# design.net
KiCad netlist of a schematic drawn in Altium Designer
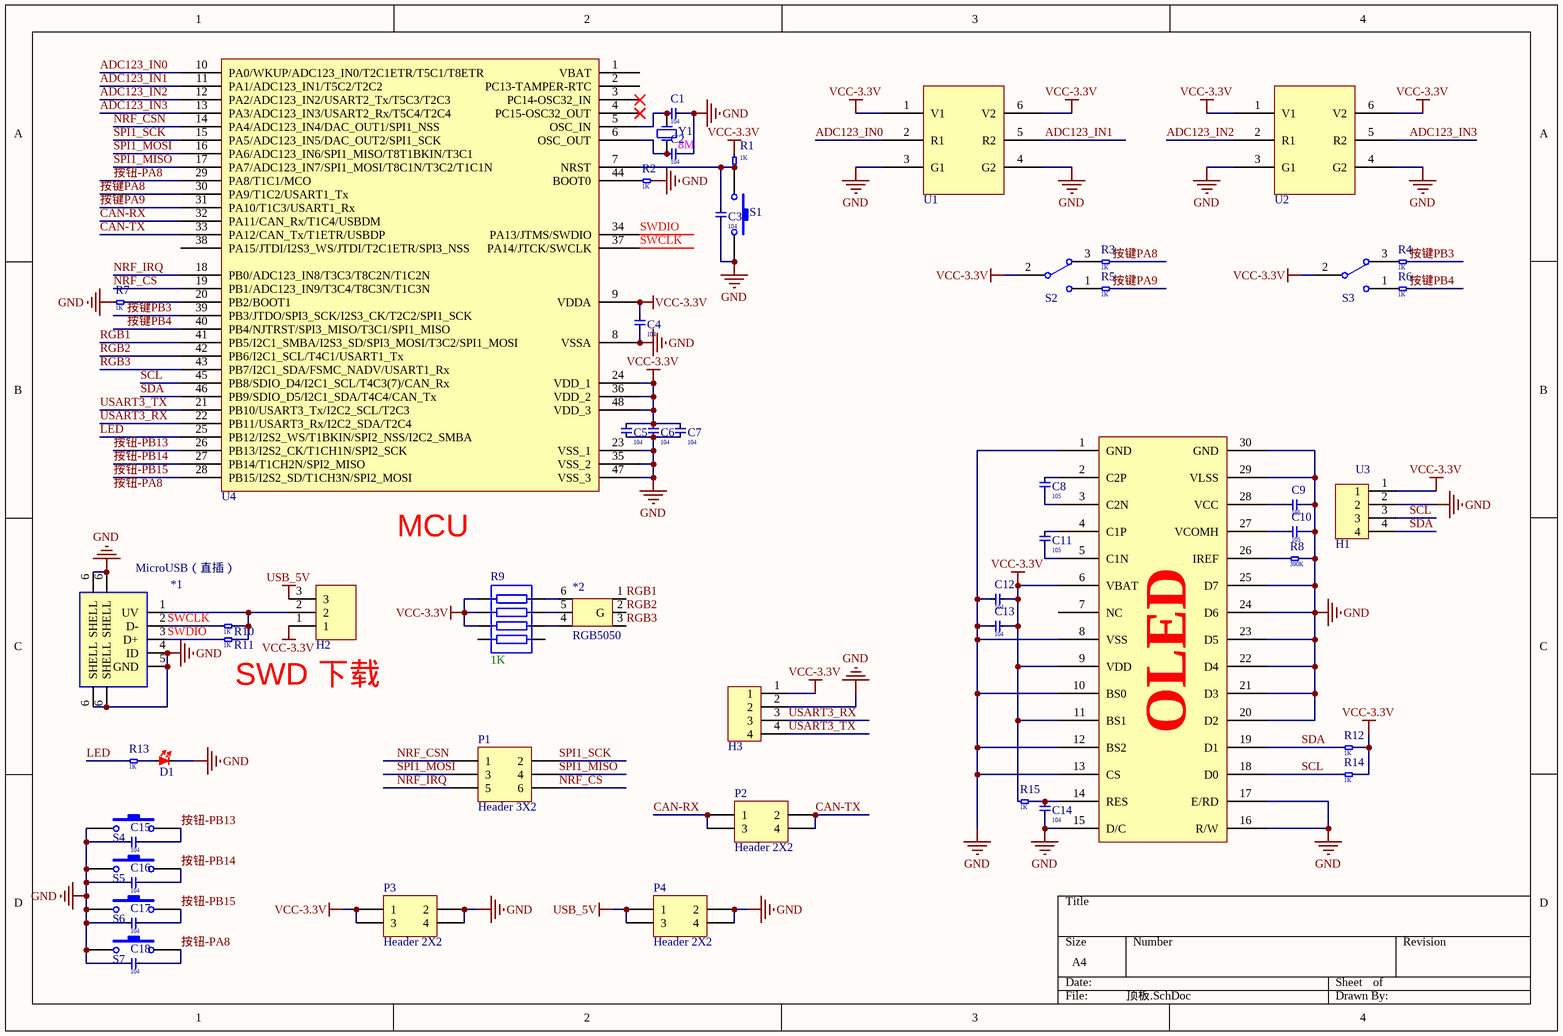
[diagram p0: 顶板.SchDoc]

(export (version "E")
  (design (tool "Eeschema 10.0.6"))
  (components
    (comp (ref "*1")
      (value "MicroUSB（直插）")
      (footprint "MicroUSB（直插）")
      (libsource (lib "固执啊啊啊啊啊（方林的封装库）7.24") (part "MicroUSB（直插）"))
    )
    (comp (ref "*2")
      (value "RGB5050")
      (footprint "RGB5050")
      (libsource (lib "xiaoze_Library") (part "RGB5050"))
    )
    (comp (ref "C1")
      (value "CAP0603")
      (footprint "CAP0603")
      (fields (field (name "ALTIUM_UNNAMED_1") "104"))
      (libsource (lib "固执啊啊啊啊啊（方林的封装库）7.24") (part "CAP0603"))
    )
    (comp (ref "C2")
      (value "CAP0603")
      (footprint "CAP0603")
      (fields (field (name "ALTIUM_UNNAMED_1") "104"))
      (libsource (lib "固执啊啊啊啊啊（方林的封装库）7.24") (part "CAP0603"))
    )
    (comp (ref "C3")
      (value "CAP0603")
      (footprint "CAP0603")
      (fields (field (name "ALTIUM_UNNAMED_1") "104"))
      (libsource (lib "固执啊啊啊啊啊（方林的封装库）7.24") (part "CAP0603"))
    )
    (comp (ref "C4")
      (value "CAP0603")
      (footprint "CAP0603")
      (fields (field (name "ALTIUM_UNNAMED_1") "104"))
      (libsource (lib "固执啊啊啊啊啊（方林的封装库）7.24") (part "CAP0603"))
    )
    (comp (ref "C5")
      (value "CAP0603")
      (footprint "CAP0603")
      (fields (field (name "ALTIUM_UNNAMED_1") "104"))
      (libsource (lib "固执啊啊啊啊啊（方林的封装库）7.24") (part "CAP0603"))
    )
    (comp (ref "C6")
      (value "CAP0603")
      (footprint "CAP0603")
      (fields (field (name "ALTIUM_UNNAMED_1") "104"))
      (libsource (lib "固执啊啊啊啊啊（方林的封装库）7.24") (part "CAP0603"))
    )
    (comp (ref "C7")
      (value "CAP0603")
      (footprint "CAP0603")
      (fields (field (name "ALTIUM_UNNAMED_1") "104"))
      (libsource (lib "固执啊啊啊啊啊（方林的封装库）7.24") (part "CAP0603"))
    )
    (comp (ref "C8")
      (value "CAP0603")
      (footprint "CAP0603")
      (fields (field (name "ALTIUM_UNNAMED_1") "105"))
      (libsource (lib "固执啊啊啊啊啊（方林的封装库）7.24") (part "CAP0603"))
    )
    (comp (ref "C9")
      (value "CAP0603")
      (footprint "CAP0603")
      (fields (field (name "ALTIUM_UNNAMED_1") "105"))
      (libsource (lib "固执啊啊啊啊啊（方林的封装库）7.24") (part "CAP0603"))
    )
    (comp (ref "C10")
      (value "CAP0603")
      (footprint "CAP0603")
      (fields (field (name "ALTIUM_UNNAMED_1") "105"))
      (libsource (lib "固执啊啊啊啊啊（方林的封装库）7.24") (part "CAP0603"))
    )
    (comp (ref "C11")
      (value "CAP0603")
      (footprint "CAP0603")
      (fields (field (name "ALTIUM_UNNAMED_1") "105"))
      (libsource (lib "固执啊啊啊啊啊（方林的封装库）7.24") (part "CAP0603"))
    )
    (comp (ref "C12")
      (value "CAP0603")
      (footprint "CAP0603")
      (fields (field (name "ALTIUM_UNNAMED_1") "104"))
      (libsource (lib "固执啊啊啊啊啊（方林的封装库）7.24") (part "CAP0603"))
    )
    (comp (ref "C13")
      (value "CAP0603")
      (footprint "CAP0603")
      (fields (field (name "ALTIUM_UNNAMED_1") "104"))
      (libsource (lib "固执啊啊啊啊啊（方林的封装库）7.24") (part "CAP0603"))
    )
    (comp (ref "C14")
      (value "CAP0603")
      (footprint "CAP0603")
      (fields (field (name "ALTIUM_UNNAMED_1") "104"))
      (libsource (lib "固执啊啊啊啊啊（方林的封装库）7.24") (part "CAP0603"))
    )
    (comp (ref "C15")
      (value "CAP0603")
      (footprint "CAP0603")
      (fields (field (name "ALTIUM_UNNAMED_1") "104"))
      (libsource (lib "固执啊啊啊啊啊（方林的封装库）7.24") (part "CAP0603"))
    )
    (comp (ref "C16")
      (value "CAP0603")
      (footprint "CAP0603")
      (fields (field (name "ALTIUM_UNNAMED_1") "104"))
      (libsource (lib "固执啊啊啊啊啊（方林的封装库）7.24") (part "CAP0603"))
    )
    (comp (ref "C17")
      (value "CAP0603")
      (footprint "CAP0603")
      (fields (field (name "ALTIUM_UNNAMED_1") "104"))
      (libsource (lib "固执啊啊啊啊啊（方林的封装库）7.24") (part "CAP0603"))
    )
    (comp (ref "C18")
      (value "CAP0603")
      (footprint "CAP0603")
      (fields (field (name "ALTIUM_UNNAMED_1") "104"))
      (libsource (lib "固执啊啊啊啊啊（方林的封装库）7.24") (part "CAP0603"))
    )
    (comp (ref "D1")
      (value "LED")
      (footprint "LED_0603_B")
      (libsource (lib "固执啊啊啊啊啊（方林的封装库）7.24") (part "LED"))
    )
    (comp (ref "H1")
      (value "H4")
      (footprint "H4")
      (description "排针")
      (libsource (lib "固执啊啊啊啊啊（方林的封装库）7.24") (part "H4"))
    )
    (comp (ref "H2")
      (value "H3")
      (footprint "H3")
      (description "排针")
      (libsource (lib "固执啊啊啊啊啊（方林的封装库）7.24") (part "H3"))
    )
    (comp (ref "H3")
      (value "H4")
      (footprint "H4")
      (description "排针")
      (libsource (lib "固执啊啊啊啊啊（方林的封装库）7.24") (part "H4"))
    )
    (comp (ref "P1")
      (value "Header 3X2")
      (footprint "HDR2X3")
      (description "Header, 3-Pin, Dual row")
      (fields (field (name "PUBLISHER") "Altium Limited"))
      (libsource (lib "Miscellaneous Connectors") (part "Header 3X2"))
    )
    (comp (ref "P2")
      (value "Header 2X2")
      (footprint "HDR2X2")
      (description "Header, 2-Pin, Dual row")
      (fields (field (name "PUBLISHER") "Altium Limited"))
      (libsource (lib "Miscellaneous Connectors") (part "Header 2X2"))
    )
    (comp (ref "P3")
      (value "Header 2X2")
      (footprint "HDR2X2")
      (description "Header, 2-Pin, Dual row")
      (fields (field (name "PUBLISHER") "Altium Limited"))
      (libsource (lib "Miscellaneous Connectors") (part "Header 2X2"))
    )
    (comp (ref "P4")
      (value "Header 2X2")
      (footprint "HDR2X2")
      (description "Header, 2-Pin, Dual row")
      (fields (field (name "PUBLISHER") "Altium Limited"))
      (libsource (lib "Miscellaneous Connectors") (part "Header 2X2"))
    )
    (comp (ref "R1")
      (value "电阻R")
      (footprint "R0603")
      (fields (field (name "ALTIUM_UNNAMED_1") "1K"))
      (libsource (lib "固执啊啊啊啊啊（方林的封装库）7.24") (part "电阻R"))
    )
    (comp (ref "R2")
      (value "电阻R")
      (footprint "R0603")
      (fields (field (name "ALTIUM_UNNAMED_1") "1K"))
      (libsource (lib "") (part "电阻R_1"))
    )
    (comp (ref "R3")
      (value "电阻R")
      (footprint "R0603")
      (fields (field (name "ALTIUM_UNNAMED_1") "1K"))
      (libsource (lib "固执啊啊啊啊啊（方林的封装库）7.24") (part "电阻R"))
    )
    (comp (ref "R4")
      (value "电阻R")
      (footprint "R0603")
      (fields (field (name "ALTIUM_UNNAMED_1") "1K"))
      (libsource (lib "固执啊啊啊啊啊（方林的封装库）7.24") (part "电阻R"))
    )
    (comp (ref "R5")
      (value "电阻R")
      (footprint "R0603")
      (fields (field (name "ALTIUM_UNNAMED_1") "1K"))
      (libsource (lib "固执啊啊啊啊啊（方林的封装库）7.24") (part "电阻R"))
    )
    (comp (ref "R6")
      (value "电阻R")
      (footprint "R0603")
      (fields (field (name "ALTIUM_UNNAMED_1") "1K"))
      (libsource (lib "固执啊啊啊啊啊（方林的封装库）7.24") (part "电阻R"))
    )
    (comp (ref "R7")
      (value "电阻R")
      (footprint "R0603")
      (fields (field (name "ALTIUM_UNNAMED_1") "1K"))
      (libsource (lib "固执啊啊啊啊啊（方林的封装库）7.24") (part "电阻R"))
    )
    (comp (ref "R8")
      (value "电阻R")
      (footprint "R0603")
      (fields (field (name "ALTIUM_UNNAMED_1") "390K"))
      (libsource (lib "固执啊啊啊啊啊（方林的封装库）7.24") (part "电阻R"))
    )
    (comp (ref "R9")
      (value "1K*4排阻")
      (footprint "1K*4排阻")
      (fields (field (name "ALTIUM_UNNAMED_1") "1K"))
      (libsource (lib "固执啊啊啊啊啊（方林的封装库）7.24") (part "1K*4排阻"))
    )
    (comp (ref "R10")
      (value "电阻R")
      (footprint "R0603")
      (fields (field (name "ALTIUM_UNNAMED_1") "1K"))
      (libsource (lib "") (part "电阻R_1"))
    )
    (comp (ref "R11")
      (value "电阻R")
      (footprint "R0603")
      (fields (field (name "ALTIUM_UNNAMED_1") "1K"))
      (libsource (lib "") (part "电阻R_1"))
    )
    (comp (ref "R12")
      (value "电阻R")
      (footprint "R0603")
      (fields (field (name "ALTIUM_UNNAMED_1") "1K"))
      (libsource (lib "固执啊啊啊啊啊（方林的封装库）7.24") (part "电阻R"))
    )
    (comp (ref "R13")
      (value "电阻R")
      (footprint "R0603")
      (fields (field (name "ALTIUM_UNNAMED_1") "1K"))
      (libsource (lib "") (part "电阻R_1"))
    )
    (comp (ref "R14")
      (value "电阻R")
      (footprint "R0603")
      (fields (field (name "ALTIUM_UNNAMED_1") "1K"))
      (libsource (lib "") (part "电阻R_1"))
    )
    (comp (ref "R15")
      (value "电阻R")
      (footprint "R0603")
      (fields (field (name "ALTIUM_UNNAMED_1") "1K"))
      (libsource (lib "固执啊啊啊啊啊（方林的封装库）7.24") (part "电阻R"))
    )
    (comp (ref "S1")
      (value "SWITCH")
      (footprint "SWITCH")
      (description "按键")
      (libsource (lib "固执啊啊啊啊啊（方林的封装库）7.24") (part "SWITCH"))
    )
    (comp (ref "S2")
      (value "拨动开关")
      (footprint "拨动开关")
      (description "扭子拨动开关")
      (libsource (lib "固执啊啊啊啊啊（方林的封装库）7.24") (part "拨动开关"))
    )
    (comp (ref "S3")
      (value "拨动开关")
      (footprint "拨动开关")
      (description "扭子拨动开关")
      (libsource (lib "固执啊啊啊啊啊（方林的封装库）7.24") (part "拨动开关"))
    )
    (comp (ref "S4")
      (value "SWITCH")
      (footprint "SWITCH")
      (description "按键")
      (libsource (lib "固执啊啊啊啊啊（方林的封装库）7.24") (part "SWITCH"))
    )
    (comp (ref "S5")
      (value "SWITCH")
      (footprint "SWITCH")
      (description "按键")
      (libsource (lib "固执啊啊啊啊啊（方林的封装库）7.24") (part "SWITCH"))
    )
    (comp (ref "S6")
      (value "SWITCH")
      (footprint "SWITCH")
      (description "按键")
      (libsource (lib "固执啊啊啊啊啊（方林的封装库）7.24") (part "SWITCH"))
    )
    (comp (ref "S7")
      (value "SWITCH")
      (footprint "SWITCH")
      (description "按键")
      (libsource (lib "固执啊啊啊啊啊（方林的封装库）7.24") (part "SWITCH"))
    )
    (comp (ref "U1")
      (value "遥控器摇杆")
      (footprint "遥控器摇杆")
      (description "摇杆")
      (libsource (lib "固执啊啊啊啊啊（方林的封装库）7.24") (part "遥控器摇杆"))
    )
    (comp (ref "U2")
      (value "遥控器摇杆")
      (footprint "遥控器摇杆")
      (description "摇杆")
      (libsource (lib "固执啊啊啊啊啊（方林的封装库）7.24") (part "遥控器摇杆"))
    )
    (comp (ref "U3") (value "OLED") (footprint "OLED") (libsource (lib "固执啊啊啊啊啊（方林的封装库）7.24") (part "OLED")))
    (comp (ref "U4")
      (value "STM32F103C8T6")
      (footprint "LQFP_48P")
      (libsource (lib "固执啊啊啊啊啊（方林的封装库）7.24") (part "STM32F103C8T6"))
    )
    (comp (ref "Y1")
      (value "XTAL")
      (footprint "XTAL")
      (description "晶振")
      (fields (field (name "ALTIUM_UNNAMED_1") "8M"))
      (libsource (lib "固执啊啊啊啊啊（方林的封装库）7.24") (part "XTAL"))
    )
  )
  (nets
    (net (code "1") (name "/ADC123_IN0") (class "Default")
      (node (ref "U1") (pin "2") (pinfunction "R1_2") (pintype "passive"))
      (node (ref "U4") (pin "10") (pinfunction "PA0/WKUP/ADC123_IN0/T2C1ETR/T5C1/T8ETR_10") (pintype "passive"))
    )
    (net (code "2") (name "/ADC123_IN1") (class "Default")
      (node (ref "U1") (pin "5") (pinfunction "R2_5") (pintype "passive"))
      (node (ref "U4") (pin "11") (pinfunction "PA1/ADC123_IN1/T5C2/T2C2_11") (pintype "passive"))
    )
    (net (code "3") (name "/ADC123_IN2") (class "Default")
      (node (ref "U2") (pin "2") (pinfunction "R1_2") (pintype "passive"))
      (node (ref "U4") (pin "12") (pinfunction "PA2/ADC123_IN2/USART2_Tx/T5C3/T2C3_12") (pintype "passive"))
    )
    (net (code "4") (name "/ADC123_IN3") (class "Default")
      (node (ref "U2") (pin "5") (pinfunction "R2_5") (pintype "passive"))
      (node (ref "U4") (pin "13") (pinfunction "PA3/ADC123_IN3/USART2_Rx/T5C4/T2C4_13") (pintype "passive"))
    )
    (net (code "5") (name "/CAN-RX") (class "Default")
      (node (ref "P2") (pin "1") (pinfunction "1_1") (pintype "passive"))
      (node (ref "P2") (pin "3") (pinfunction "3_3") (pintype "passive"))
      (node (ref "U4") (pin "32") (pinfunction "PA11/CAN_Rx/T1C4/USBDM_32") (pintype "passive"))
    )
    (net (code "6") (name "/CAN-TX") (class "Default")
      (node (ref "P2") (pin "2") (pinfunction "2_2") (pintype "passive"))
      (node (ref "P2") (pin "4") (pinfunction "4_4") (pintype "passive"))
      (node (ref "U4") (pin "33") (pinfunction "PA12/CAN_Tx/T1ETR/USBDP_33") (pintype "passive"))
    )
    (net (code "7") (name "/LED") (class "Default")
      (node (ref "R13") (pin "1") (pintype "passive"))
      (node (ref "U4") (pin "25") (pinfunction "PB12/I2S2_WS/T1BKIN/SPI2_NSS/I2C2_SMBA_25") (pintype "passive"))
    )
    (net (code "8") (name "/NRF_CS") (class "Default")
      (node (ref "P1") (pin "6") (pinfunction "6_6") (pintype "passive"))
      (node (ref "U4") (pin "19") (pinfunction "PB1/ADC123_IN9/T3C4/T8C3N/T1C3N_19") (pintype "passive"))
    )
    (net (code "9") (name "/NRF_CSN") (class "Default")
      (node (ref "P1") (pin "1") (pinfunction "1_1") (pintype "passive"))
      (node (ref "U4") (pin "14") (pinfunction "PA4/ADC123_IN4/DAC_OUT1/SPI1_NSS_14") (pintype "passive"))
    )
    (net (code "10") (name "/NRF_IRQ") (class "Default")
      (node (ref "P1") (pin "5") (pinfunction "5_5") (pintype "passive"))
      (node (ref "U4") (pin "18") (pinfunction "PB0/ADC123_IN8/T3C3/T8C2N/T1C2N_18") (pintype "passive"))
    )
    (net (code "11") (name "/RGB1") (class "Default")
      (node (ref "*2") (pin "1") (pinfunction "G_1") (pintype "passive"))
      (node (ref "U4") (pin "41") (pinfunction "PB5/I2C1_SMBA/I2S3_SD/SPI3_MOSI/T3C2/SPI1_MOSI_41") (pintype "passive"))
    )
    (net (code "12") (name "/RGB2") (class "Default")
      (node (ref "*2") (pin "2") (pinfunction "G_2") (pintype "passive"))
      (node (ref "U4") (pin "42") (pinfunction "PB6/I2C1_SCL/T4C1/USART1_Tx_42") (pintype "passive"))
    )
    (net (code "13") (name "/RGB3") (class "Default")
      (node (ref "*2") (pin "3") (pinfunction "G_3") (pintype "passive"))
      (node (ref "U4") (pin "43") (pinfunction "PB7/I2C1_SDA/FSMC_NADV/USART1_Rx_43") (pintype "passive"))
    )
    (net (code "14") (name "/SCL") (class "Default")
      (node (ref "H1") (pin "3") (pinfunction "3_3") (pintype "passive"))
      (node (ref "R14") (pin "1") (pintype "passive"))
      (node (ref "U3") (pin "18") (pinfunction "D0_18") (pintype "passive"))
      (node (ref "U4") (pin "45") (pinfunction "PB8/SDIO_D4/I2C1_SCL/T4C3(7)/CAN_Rx_45") (pintype "passive"))
    )
    (net (code "15") (name "/SDA") (class "Default")
      (node (ref "H1") (pin "4") (pinfunction "4_4") (pintype "passive"))
      (node (ref "R12") (pin "2") (pintype "passive"))
      (node (ref "U3") (pin "19") (pinfunction "D1_19") (pintype "passive"))
      (node (ref "U4") (pin "46") (pinfunction "PB9/SDIO_D5/I2C1_SDA/T4C4/CAN_Tx_46") (pintype "passive"))
    )
    (net (code "16") (name "/SPI1_MISO") (class "Default")
      (node (ref "P1") (pin "4") (pinfunction "4_4") (pintype "passive"))
      (node (ref "U4") (pin "17") (pinfunction "PA7/ADC123_IN7/SPI1_MOSI/T8C1N/T3C2/T1C1N_17") (pintype "passive"))
    )
    (net (code "17") (name "/SPI1_MOSI") (class "Default")
      (node (ref "P1") (pin "3") (pinfunction "3_3") (pintype "passive"))
      (node (ref "U4") (pin "16") (pinfunction "PA6/ADC123_IN6/SPI1_MISO/T8T1BKIN/T3C1_16") (pintype "passive"))
    )
    (net (code "18") (name "/SPI1_SCK") (class "Default")
      (node (ref "P1") (pin "2") (pinfunction "2_2") (pintype "passive"))
      (node (ref "U4") (pin "15") (pinfunction "PA5/ADC123_IN5/DAC_OUT2/SPI1_SCK_15") (pintype "passive"))
    )
    (net (code "19") (name "/SWCLK") (class "Default")
      (node (ref "*1") (pin "2") (pinfunction "D-_2") (pintype "passive"))
      (node (ref "R10") (pin "1") (pintype "passive"))
      (node (ref "U4") (pin "37") (pinfunction "PA14/JTCK/SWCLK_37") (pintype "passive"))
    )
    (net (code "20") (name "/SWDIO") (class "Default")
      (node (ref "*1") (pin "3") (pinfunction "D+_3") (pintype "passive"))
      (node (ref "R11") (pin "1") (pintype "passive"))
      (node (ref "U4") (pin "34") (pinfunction "PA13/JTMS/SWDIO_34") (pintype "passive"))
    )
    (net (code "21") (name "/USART3_RX") (class "Default")
      (node (ref "H3") (pin "3") (pinfunction "3_3") (pintype "passive"))
      (node (ref "U4") (pin "22") (pinfunction "PB11/USART3_Rx/I2C2_SDA/T2C4_22") (pintype "passive"))
    )
    (net (code "22") (name "/USART3_TX") (class "Default")
      (node (ref "H3") (pin "4") (pinfunction "4_4") (pintype "passive"))
      (node (ref "U4") (pin "21") (pinfunction "PB10/USART3_Tx/I2C2_SCL/T2C3_21") (pintype "passive"))
    )
    (net (code "23") (name "/按钮-PA8") (class "Default")
      (node (ref "C18") (pin "1") (pinfunction "1_1") (pintype "passive"))
      (node (ref "S7") (pin "2") (pinfunction "2_2") (pintype "passive"))
      (node (ref "U4") (pin "29") (pinfunction "PA8/T1C1/MCO_29") (pintype "passive"))
    )
    (net (code "24") (name "/按钮-PB13") (class "Default")
      (node (ref "C15") (pin "1") (pinfunction "1_1") (pintype "passive"))
      (node (ref "S4") (pin "2") (pinfunction "2_2") (pintype "passive"))
      (node (ref "U4") (pin "26") (pinfunction "PB13/I2S2_CK/T1CH1N/SPI2_SCK_26") (pintype "passive"))
    )
    (net (code "25") (name "/按钮-PB14") (class "Default")
      (node (ref "C16") (pin "1") (pinfunction "1_1") (pintype "passive"))
      (node (ref "S5") (pin "2") (pinfunction "2_2") (pintype "passive"))
      (node (ref "U4") (pin "27") (pinfunction "PB14/T1CH2N/SPI2_MISO_27") (pintype "passive"))
    )
    (net (code "26") (name "/按钮-PB15") (class "Default")
      (node (ref "C17") (pin "1") (pinfunction "1_1") (pintype "passive"))
      (node (ref "S6") (pin "2") (pinfunction "2_2") (pintype "passive"))
      (node (ref "U4") (pin "28") (pinfunction "PB15/I2S2_SD/T1CH3N/SPI2_MOSI_28") (pintype "passive"))
    )
    (net (code "27") (name "/按键PA8") (class "Default")
      (node (ref "R3") (pin "1") (pintype "passive"))
      (node (ref "U4") (pin "30") (pinfunction "PA9/T1C2/USART1_Tx_30") (pintype "passive"))
    )
    (net (code "28") (name "/按键PA9") (class "Default")
      (node (ref "R5") (pin "1") (pintype "passive"))
      (node (ref "U4") (pin "31") (pinfunction "PA10/T1C3/USART1_Rx_31") (pintype "passive"))
    )
    (net (code "29") (name "/按键PB3") (class "Default")
      (node (ref "R4") (pin "1") (pintype "passive"))
      (node (ref "U4") (pin "39") (pinfunction "PB3/JTDO/SPI3_SCK/I2S3_CK/T2C2/SPI1_SCK_39") (pintype "passive"))
    )
    (net (code "30") (name "/按键PB4") (class "Default")
      (node (ref "R6") (pin "1") (pintype "passive"))
      (node (ref "U4") (pin "40") (pinfunction "PB4/NJTRST/SPI3_MISO/T3C1/SPI1_MISO_40") (pintype "passive"))
    )
    (net (code "31") (name "GND") (class "Default")
      (node (ref "*1") (pin "4") (pinfunction "ID_4") (pintype "passive"))
      (node (ref "*1") (pin "5") (pinfunction "GND_5") (pintype "passive"))
      (node (ref "*1") (pin "6") (pinfunction "SHELL_6") (pintype "passive"))
      (node (ref "C1") (pin "2") (pinfunction "2_2") (pintype "passive"))
      (node (ref "C10") (pin "1") (pinfunction "1_1") (pintype "passive"))
      (node (ref "C12") (pin "2") (pinfunction "2_2") (pintype "passive"))
      (node (ref "C13") (pin "2") (pinfunction "2_2") (pintype "passive"))
      (node (ref "C14") (pin "1") (pinfunction "1_1") (pintype "passive"))
      (node (ref "C15") (pin "2") (pinfunction "2_2") (pintype "passive"))
      (node (ref "C16") (pin "2") (pinfunction "2_2") (pintype "passive"))
      (node (ref "C17") (pin "2") (pinfunction "2_2") (pintype "passive"))
      (node (ref "C18") (pin "2") (pinfunction "2_2") (pintype "passive"))
      (node (ref "C2") (pin "2") (pinfunction "2_2") (pintype "passive"))
      (node (ref "C3") (pin "1") (pinfunction "1_1") (pintype "passive"))
      (node (ref "C4") (pin "1") (pinfunction "1_1") (pintype "passive"))
      (node (ref "C5") (pin "1") (pinfunction "1_1") (pintype "passive"))
      (node (ref "C6") (pin "1") (pinfunction "1_1") (pintype "passive"))
      (node (ref "C7") (pin "1") (pinfunction "1_1") (pintype "passive"))
      (node (ref "C9") (pin "1") (pinfunction "1_1") (pintype "passive"))
      (node (ref "D1") (pin "2") (pintype "passive"))
      (node (ref "H1") (pin "2") (pinfunction "2_2") (pintype "passive"))
      (node (ref "H3") (pin "2") (pinfunction "2_2") (pintype "passive"))
      (node (ref "P3") (pin "2") (pinfunction "2_2") (pintype "passive"))
      (node (ref "P3") (pin "4") (pinfunction "4_4") (pintype "passive"))
      (node (ref "P4") (pin "2") (pinfunction "2_2") (pintype "passive"))
      (node (ref "P4") (pin "4") (pinfunction "4_4") (pintype "passive"))
      (node (ref "R2") (pin "2") (pintype "passive"))
      (node (ref "R7") (pin "2") (pintype "passive"))
      (node (ref "R8") (pin "1") (pintype "passive"))
      (node (ref "S1") (pin "2") (pinfunction "2_2") (pintype "passive"))
      (node (ref "S4") (pin "1") (pinfunction "1_1") (pintype "passive"))
      (node (ref "S5") (pin "1") (pinfunction "1_1") (pintype "passive"))
      (node (ref "S6") (pin "1") (pinfunction "1_1") (pintype "passive"))
      (node (ref "S7") (pin "1") (pinfunction "1_1") (pintype "passive"))
      (node (ref "U1") (pin "3") (pinfunction "G1_3") (pintype "passive"))
      (node (ref "U1") (pin "4") (pinfunction "G2_4") (pintype "passive"))
      (node (ref "U2") (pin "3") (pinfunction "G1_3") (pintype "passive"))
      (node (ref "U2") (pin "4") (pinfunction "G2_4") (pintype "passive"))
      (node (ref "U3") (pin "1") (pinfunction "GND_1") (pintype "passive"))
      (node (ref "U3") (pin "10") (pinfunction "BS0_10") (pintype "passive"))
      (node (ref "U3") (pin "12") (pinfunction "BS2_12") (pintype "passive"))
      (node (ref "U3") (pin "13") (pinfunction "CS_13") (pintype "passive"))
      (node (ref "U3") (pin "15") (pinfunction "D/C_15") (pintype "passive"))
      (node (ref "U3") (pin "16") (pinfunction "R/W_16") (pintype "passive"))
      (node (ref "U3") (pin "17") (pinfunction "E/RD_17") (pintype "passive"))
      (node (ref "U3") (pin "20") (pinfunction "D2_20") (pintype "passive"))
      (node (ref "U3") (pin "21") (pinfunction "D3_21") (pintype "passive"))
      (node (ref "U3") (pin "22") (pinfunction "D4_22") (pintype "passive"))
      (node (ref "U3") (pin "23") (pinfunction "D5_23") (pintype "passive"))
      (node (ref "U3") (pin "24") (pinfunction "D6_24") (pintype "passive"))
      (node (ref "U3") (pin "25") (pinfunction "D7_25") (pintype "passive"))
      (node (ref "U3") (pin "29") (pinfunction "VLSS_29") (pintype "passive"))
      (node (ref "U3") (pin "30") (pinfunction "GND_30") (pintype "passive"))
      (node (ref "U3") (pin "8") (pinfunction "VSS_8") (pintype "passive"))
      (node (ref "U4") (pin "23") (pinfunction "VSS_1_23") (pintype "passive"))
      (node (ref "U4") (pin "35") (pinfunction "VSS_2_35") (pintype "passive"))
      (node (ref "U4") (pin "47") (pinfunction "VSS_3_47") (pintype "passive"))
      (node (ref "U4") (pin "8") (pinfunction "VSSA_8") (pintype "passive"))
    )
    (net (code "32") (name "Net-(*1-UV)") (class "Default")
      (node (ref "*1") (pin "1") (pinfunction "UV_1") (pintype "passive"))
      (node (ref "H2") (pin "2") (pinfunction "2_2") (pintype "passive"))
      (node (ref "R10") (pin "2") (pintype "passive"))
      (node (ref "R11") (pin "2") (pintype "passive"))
    )
    (net (code "33") (name "Net-(*2-G-Pad4)") (class "Default")
      (node (ref "*2") (pin "4") (pinfunction "G_4") (pintype "passive"))
      (node (ref "R9") (pin "6") (pintype "passive"))
    )
    (net (code "34") (name "Net-(*2-G-Pad5)") (class "Default")
      (node (ref "*2") (pin "5") (pinfunction "G_5") (pintype "passive"))
      (node (ref "R9") (pin "4") (pintype "passive"))
    )
    (net (code "35") (name "Net-(*2-G-Pad6)") (class "Default")
      (node (ref "*2") (pin "6") (pinfunction "G_6") (pintype "passive"))
      (node (ref "R9") (pin "2") (pintype "passive"))
    )
    (net (code "36") (name "Net-(D1-Pad1)") (class "Default")
      (node (ref "D1") (pin "1") (pintype "passive"))
      (node (ref "R13") (pin "2") (pintype "passive"))
    )
    (net (code "37") (name "Net-(R3-Pad2)") (class "Default")
      (node (ref "R3") (pin "2") (pintype "passive"))
      (node (ref "S2") (pin "3") (pinfunction "3_3") (pintype "passive"))
    )
    (net (code "38") (name "Net-(R4-Pad2)") (class "Default")
      (node (ref "R4") (pin "2") (pintype "passive"))
      (node (ref "S3") (pin "3") (pinfunction "3_3") (pintype "passive"))
    )
    (net (code "39") (name "Net-(R5-Pad2)") (class "Default")
      (node (ref "R5") (pin "2") (pintype "passive"))
      (node (ref "S2") (pin "1") (pinfunction "1_1") (pintype "passive"))
    )
    (net (code "40") (name "Net-(R6-Pad2)") (class "Default")
      (node (ref "R6") (pin "2") (pintype "passive"))
      (node (ref "S3") (pin "1") (pinfunction "1_1") (pintype "passive"))
    )
    (net (code "41") (name "Net-(U3-C1N)") (class "Default")
      (node (ref "C11") (pin "1") (pinfunction "1_1") (pintype "passive"))
      (node (ref "U3") (pin "5") (pinfunction "C1N_5") (pintype "passive"))
    )
    (net (code "42") (name "Net-(U3-C1P)") (class "Default")
      (node (ref "C11") (pin "2") (pinfunction "2_2") (pintype "passive"))
      (node (ref "U3") (pin "4") (pinfunction "C1P_4") (pintype "passive"))
    )
    (net (code "43") (name "Net-(U3-C2N)") (class "Default")
      (node (ref "C8") (pin "1") (pinfunction "1_1") (pintype "passive"))
      (node (ref "U3") (pin "3") (pinfunction "C2N_3") (pintype "passive"))
    )
    (net (code "44") (name "Net-(U3-C2P)") (class "Default")
      (node (ref "C8") (pin "2") (pinfunction "2_2") (pintype "passive"))
      (node (ref "U3") (pin "2") (pinfunction "C2P_2") (pintype "passive"))
    )
    (net (code "45") (name "Net-(U3-IREF)") (class "Default")
      (node (ref "R8") (pin "2") (pintype "passive"))
      (node (ref "U3") (pin "26") (pinfunction "IREF_26") (pintype "passive"))
    )
    (net (code "46") (name "Net-(U3-RES)") (class "Default")
      (node (ref "C14") (pin "2") (pinfunction "2_2") (pintype "passive"))
      (node (ref "R15") (pin "1") (pintype "passive"))
      (node (ref "U3") (pin "14") (pinfunction "RES_14") (pintype "passive"))
    )
    (net (code "47") (name "Net-(U3-VCC)") (class "Default")
      (node (ref "C9") (pin "2") (pinfunction "2_2") (pintype "passive"))
      (node (ref "U3") (pin "28") (pinfunction "VCC_28") (pintype "passive"))
    )
    (net (code "48") (name "Net-(U3-VCOMH)") (class "Default")
      (node (ref "C10") (pin "2") (pinfunction "2_2") (pintype "passive"))
      (node (ref "U3") (pin "27") (pinfunction "VCOMH_27") (pintype "passive"))
    )
    (net (code "49") (name "Net-(U4-BOOT0)") (class "Default")
      (node (ref "R2") (pin "1") (pintype "passive"))
      (node (ref "U4") (pin "44") (pinfunction "BOOT0_44") (pintype "passive"))
    )
    (net (code "50") (name "Net-(U4-NRST)") (class "Default")
      (node (ref "C3") (pin "2") (pinfunction "2_2") (pintype "passive"))
      (node (ref "R1") (pin "1") (pintype "passive"))
      (node (ref "S1") (pin "1") (pinfunction "1_1") (pintype "passive"))
      (node (ref "U4") (pin "7") (pinfunction "NRST_7") (pintype "passive"))
    )
    (net (code "51") (name "Net-(U4-OSC_IN)") (class "Default")
      (node (ref "C1") (pin "1") (pinfunction "1_1") (pintype "passive"))
      (node (ref "U4") (pin "5") (pinfunction "OSC_IN_5") (pintype "passive"))
      (node (ref "Y1") (pin "2") (pinfunction "OSC2_2") (pintype "passive"))
    )
    (net (code "52") (name "Net-(U4-OSC_OUT)") (class "Default")
      (node (ref "C2") (pin "1") (pinfunction "1_1") (pintype "passive"))
      (node (ref "U4") (pin "6") (pinfunction "OSC_OUT_6") (pintype "passive"))
      (node (ref "Y1") (pin "1") (pinfunction "OSC1_1") (pintype "passive"))
    )
    (net (code "53") (name "Net-(U4-PB2{slash}BOOT1)") (class "Default")
      (node (ref "R7") (pin "1") (pintype "passive"))
      (node (ref "U4") (pin "20") (pinfunction "PB2/BOOT1_20") (pintype "passive"))
    )
    (net (code "54") (name "USB_5V") (class "Default")
      (node (ref "H2") (pin "3") (pinfunction "3_3") (pintype "passive"))
      (node (ref "P4") (pin "1") (pinfunction "1_1") (pintype "passive"))
      (node (ref "P4") (pin "3") (pinfunction "3_3") (pintype "passive"))
    )
    (net (code "55") (name "VCC-3.3V") (class "Default")
      (node (ref "C12") (pin "1") (pinfunction "1_1") (pintype "passive"))
      (node (ref "C13") (pin "1") (pinfunction "1_1") (pintype "passive"))
      (node (ref "C4") (pin "2") (pinfunction "2_2") (pintype "passive"))
      (node (ref "C5") (pin "2") (pinfunction "2_2") (pintype "passive"))
      (node (ref "C6") (pin "2") (pinfunction "2_2") (pintype "passive"))
      (node (ref "C7") (pin "2") (pinfunction "2_2") (pintype "passive"))
      (node (ref "H1") (pin "1") (pinfunction "1_1") (pintype "passive"))
      (node (ref "H2") (pin "1") (pinfunction "1_1") (pintype "passive"))
      (node (ref "H3") (pin "1") (pinfunction "1_1") (pintype "passive"))
      (node (ref "P3") (pin "1") (pinfunction "1_1") (pintype "passive"))
      (node (ref "P3") (pin "3") (pinfunction "3_3") (pintype "passive"))
      (node (ref "R1") (pin "2") (pintype "passive"))
      (node (ref "R12") (pin "1") (pintype "passive"))
      (node (ref "R14") (pin "2") (pintype "passive"))
      (node (ref "R15") (pin "2") (pintype "passive"))
      (node (ref "R9") (pin "1") (pintype "passive"))
      (node (ref "R9") (pin "3") (pintype "passive"))
      (node (ref "R9") (pin "5") (pintype "passive"))
      (node (ref "S2") (pin "2") (pinfunction "2_2") (pintype "passive"))
      (node (ref "S3") (pin "2") (pinfunction "2_2") (pintype "passive"))
      (node (ref "U1") (pin "1") (pinfunction "V1_1") (pintype "passive"))
      (node (ref "U1") (pin "6") (pinfunction "V2_6") (pintype "passive"))
      (node (ref "U2") (pin "1") (pinfunction "V1_1") (pintype "passive"))
      (node (ref "U2") (pin "6") (pinfunction "V2_6") (pintype "passive"))
      (node (ref "U3") (pin "11") (pinfunction "BS1_11") (pintype "passive"))
      (node (ref "U3") (pin "6") (pinfunction "VBAT_6") (pintype "passive"))
      (node (ref "U3") (pin "9") (pinfunction "VDD_9") (pintype "passive"))
      (node (ref "U4") (pin "24") (pinfunction "VDD_1_24") (pintype "passive"))
      (node (ref "U4") (pin "36") (pinfunction "VDD_2_36") (pintype "passive"))
      (node (ref "U4") (pin "48") (pinfunction "VDD_3_48") (pintype "passive"))
      (node (ref "U4") (pin "9") (pinfunction "VDDA_9") (pintype "passive"))
    )
    (net (code "56") (name "unconnected-(R9-Pad7)") (class "Default")
      (node (ref "R9") (pin "7") (pintype "passive"))
    )
    (net (code "57") (name "unconnected-(R9-Pad8)") (class "Default")
      (node (ref "R9") (pin "8") (pintype "passive"))
    )
    (net (code "58") (name "unconnected-(U3-NC-Pad7)") (class "Default")
      (node (ref "U3") (pin "7") (pinfunction "NC_7") (pintype "passive"))
    )
    (net (code "59") (name "unconnected-(U4-PA15{slash}JTDI{slash}I2S3_WS{slash}JTDI{slash}T2C1ETR{slash}SPI3_NSS-Pad38)") (class "Default")
      (node (ref "U4") (pin "38") (pinfunction "PA15/JTDI/I2S3_WS/JTDI/T2C1ETR/SPI3_NSS_38") (pintype "passive"))
    )
    (net (code "60") (name "unconnected-(U4-PC13-TAMPER-RTC-Pad2)") (class "Default")
      (node (ref "U4") (pin "2") (pinfunction "PC13-TAMPER-RTC_2") (pintype "passive"))
    )
    (net (code "61") (name "unconnected-(U4-PC14-OSC32_IN-Pad3)") (class "Default")
      (node (ref "U4") (pin "3") (pinfunction "PC14-OSC32_IN_3") (pintype "passive+no_connect"))
    )
    (net (code "62") (name "unconnected-(U4-PC15-OSC32_OUT-Pad4)") (class "Default")
      (node (ref "U4") (pin "4") (pinfunction "PC15-OSC32_OUT_4") (pintype "passive+no_connect"))
    )
    (net (code "63") (name "unconnected-(U4-VBAT-Pad1)") (class "Default")
      (node (ref "U4") (pin "1") (pinfunction "VBAT_1") (pintype "passive"))
    )
  )
)
